# ble_shield.net
KiCad netlist of a schematic drawn in EAGLE
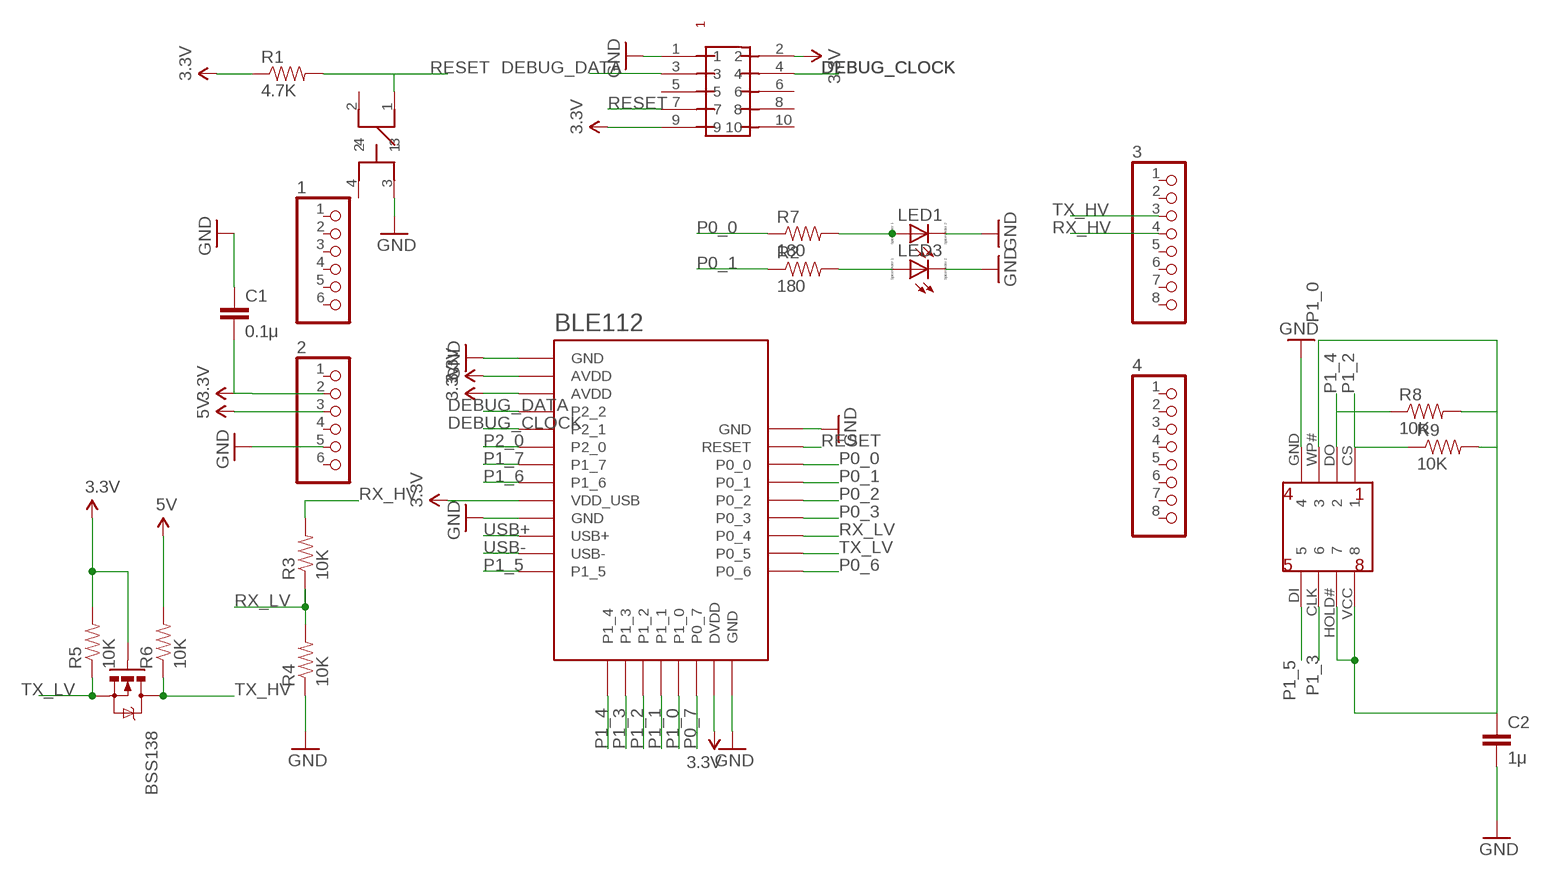
[diagram p0: schematic, sheet 1]

(export (version "E")
  (design (tool "Eeschema 10.0.6"))
  (components
    (comp (ref "1")
      (value "PINHD-1X6CB")
      (footprint "eagle-import:1X06-CLEANBIG")
      (libsource (lib "eagle-import") (part "PINHD-1X6CB"))
    )
    (comp (ref "2")
      (value "PINHD-1X6CB")
      (footprint "eagle-import:1X06-CLEANBIG")
      (libsource (lib "eagle-import") (part "PINHD-1X6CB"))
    )
    (comp (ref "3")
      (value "PINHD-1X8CLEANBIG")
      (footprint "eagle-import:1X08-CLEANBIG")
      (libsource (lib "eagle-import") (part "PINHD-1X8CLEANBIG"))
    )
    (comp (ref "4")
      (value "PINHD-1X8CLEANBIG")
      (footprint "eagle-import:1X08-CLEANBIG")
      (libsource (lib "eagle-import") (part "PINHD-1X8CLEANBIG"))
    )
    (comp (ref "BLE112")
      (value "SF-BLUEGIGA_BLE112-A-VISUAL")
      (footprint "eagle-import:SF-BLUEGIGA_BLE112-A")
      (libsource (lib "eagle-import") (part "SF-BLUEGIGA_BLE112-A-VISUAL"))
    )
    (comp (ref "BSS138")
      (value "MOSFET-NCHANNELSMD")
      (footprint "eagle-import:SOT23-3")
      (libsource (lib "eagle-import") (part "MOSFET-NCHANNELSMD"))
    )
    (comp (ref "C1")
      (value "0.1μ")
      (footprint "eagle-import:0603-CAP")
      (libsource (lib "eagle-import") (part "CAP0603-CAP"))
    )
    (comp (ref "C2")
      (value "1μ")
      (footprint "eagle-import:0603-CAP")
      (libsource (lib "eagle-import") (part "CAP0603-CAP"))
    )
    (comp (ref "LED1")
      (value "LED_ESML0603")
      (footprint "eagle-import:LED_SML0603")
      (libsource (lib "eagle-import") (part "LED_ESML0603"))
    )
    (comp (ref "LED3")
      (value "LED_ESML0603")
      (footprint "eagle-import:LED_SML0603")
      (libsource (lib "eagle-import") (part "LED_ESML0603"))
    )
    (comp (ref "R1")
      (value "4.7K")
      (footprint "eagle-import:0603-RES")
      (libsource (lib "eagle-import") (part "RESISTOR0603-RES"))
    )
    (comp (ref "R2")
      (value "180")
      (footprint "eagle-import:0603-RES")
      (libsource (lib "eagle-import") (part "RESISTOR0603-RES"))
    )
    (comp (ref "R3")
      (value "10K")
      (footprint "eagle-import:0603-RES")
      (libsource (lib "eagle-import") (part "RESISTOR0603-RES"))
    )
    (comp (ref "R4")
      (value "10K")
      (footprint "eagle-import:0603-RES")
      (libsource (lib "eagle-import") (part "RESISTOR0603-RES"))
    )
    (comp (ref "R5")
      (value "10K")
      (footprint "eagle-import:0603-RES")
      (libsource (lib "eagle-import") (part "RESISTOR0603-RES"))
    )
    (comp (ref "R6")
      (value "10K")
      (footprint "eagle-import:0603-RES")
      (libsource (lib "eagle-import") (part "RESISTOR0603-RES"))
    )
    (comp (ref "R7")
      (value "180")
      (footprint "eagle-import:0603-RES")
      (libsource (lib "eagle-import") (part "RESISTOR0603-RES"))
    )
    (comp (ref "R8")
      (value "10K")
      (footprint "eagle-import:0603-RES")
      (libsource (lib "eagle-import") (part "RESISTOR0603-RES"))
    )
    (comp (ref "R9")
      (value "10K")
      (footprint "eagle-import:0603-RES")
      (libsource (lib "eagle-import") (part "RESISTOR0603-RES"))
    )
    (comp (ref "U$1")
      (value "PIN-HEADER-SMT(1.27MM)2X5")
      (footprint "eagle-import:PIN-HEADER-SMT(1.27MM)2X5")
      (libsource (lib "eagle-import") (part "PIN-HEADER-SMT(1.27MM)2X5"))
    )
    (comp (ref "U$4")
      (value "SWITCH-LS6J2M-T")
      (footprint "eagle-import:SWICTH-LS6J2M-T")
      (libsource (lib "eagle-import") (part "SWITCH-LS6J2M-T"))
    )
    (comp (ref "U$7")
      (value "FLASH-MEMORY-2M(WINBOND)")
      (footprint "eagle-import:FLASH-MEMORY-2M(WINBOND)")
      (libsource (lib "eagle-import") (part "FLASH-MEMORY-2M(WINBOND)"))
    )
  )
  (nets
    (net (code "1") (name "/DEBUG_CLOCK") (class "Default")
      (node (ref "BLE112") (pin "P2_1") (pinfunction "P2_1_P2_1") (pintype "bidirectional"))
      (node (ref "U$1") (pin "4") (pinfunction "4_4") (pintype "bidirectional"))
    )
    (net (code "2") (name "/DEBUG_DATA") (class "Default")
      (node (ref "BLE112") (pin "P2_2") (pinfunction "P2_2_P2_2") (pintype "bidirectional"))
      (node (ref "U$1") (pin "3") (pinfunction "3_3") (pintype "bidirectional"))
    )
    (net (code "3") (name "/P0_0") (class "Default")
      (node (ref "BLE112") (pin "P0_0") (pinfunction "P0_0_P0_0") (pintype "bidirectional"))
      (node (ref "R7") (pin "1") (pinfunction "1_1") (pintype "passive"))
    )
    (net (code "4") (name "/P0_1") (class "Default")
      (node (ref "BLE112") (pin "P0_1") (pinfunction "P0_1_P0_1") (pintype "bidirectional"))
      (node (ref "R2") (pin "1") (pinfunction "1_1") (pintype "passive"))
    )
    (net (code "5") (name "/P0_2") (class "Default")
      (node (ref "BLE112") (pin "P0_2") (pinfunction "P0_2_P0_2") (pintype "bidirectional"))
    )
    (net (code "6") (name "/P0_3") (class "Default")
      (node (ref "BLE112") (pin "P0_3") (pinfunction "P0_3_P0_3") (pintype "bidirectional"))
    )
    (net (code "7") (name "/P0_6") (class "Default")
      (node (ref "BLE112") (pin "P0_6") (pinfunction "P0_6_P0_6") (pintype "bidirectional"))
    )
    (net (code "8") (name "/P0_7") (class "Default")
      (node (ref "BLE112") (pin "P0_7") (pinfunction "P0_7_P0_7") (pintype "bidirectional"))
    )
    (net (code "9") (name "/P1_0") (class "Default")
      (node (ref "BLE112") (pin "P1_0") (pinfunction "P1_0_P1_0") (pintype "bidirectional"))
      (node (ref "C2") (pin "1") (pinfunction "1_1") (pintype "passive"))
      (node (ref "R8") (pin "2") (pinfunction "2_2") (pintype "passive"))
      (node (ref "R9") (pin "2") (pinfunction "2_2") (pintype "passive"))
      (node (ref "U$7") (pin "HOLD#") (pinfunction "7_HOLD#") (pintype "bidirectional"))
      (node (ref "U$7") (pin "VCC") (pinfunction "8_VCC") (pintype "bidirectional"))
      (node (ref "U$7") (pin "WP#") (pinfunction "3_WP#") (pintype "bidirectional"))
    )
    (net (code "10") (name "/P1_1") (class "Default")
      (node (ref "BLE112") (pin "P1_1") (pinfunction "P1_1_P1_1") (pintype "bidirectional"))
    )
    (net (code "11") (name "/P1_2") (class "Default")
      (node (ref "BLE112") (pin "P1_2") (pinfunction "P1_2_P1_2") (pintype "bidirectional"))
      (node (ref "R9") (pin "1") (pinfunction "1_1") (pintype "passive"))
      (node (ref "U$7") (pin "CS") (pinfunction "1_CS") (pintype "bidirectional"))
    )
    (net (code "12") (name "/P1_3") (class "Default")
      (node (ref "BLE112") (pin "P1_3") (pinfunction "P1_3_P1_3") (pintype "bidirectional"))
      (node (ref "U$7") (pin "CLK") (pinfunction "6_CLK") (pintype "bidirectional"))
    )
    (net (code "13") (name "/P1_4") (class "Default")
      (node (ref "BLE112") (pin "P1_4") (pinfunction "P1_4_P1_4") (pintype "bidirectional"))
      (node (ref "R8") (pin "1") (pinfunction "1_1") (pintype "passive"))
      (node (ref "U$7") (pin "DO") (pinfunction "2_DO") (pintype "bidirectional"))
    )
    (net (code "14") (name "/P1_5") (class "Default")
      (node (ref "BLE112") (pin "P1_5") (pinfunction "P1_5_P1_5") (pintype "bidirectional"))
      (node (ref "U$7") (pin "DI") (pinfunction "5_DI") (pintype "bidirectional"))
    )
    (net (code "15") (name "/P1_6") (class "Default")
      (node (ref "BLE112") (pin "P1_6") (pinfunction "P1_6_P1_6") (pintype "bidirectional"))
    )
    (net (code "16") (name "/P1_7") (class "Default")
      (node (ref "BLE112") (pin "P1_7") (pinfunction "P1_7_P1_7") (pintype "bidirectional"))
    )
    (net (code "17") (name "/P2_0") (class "Default")
      (node (ref "BLE112") (pin "P2_0") (pinfunction "P2_0_P2_0") (pintype "bidirectional"))
    )
    (net (code "18") (name "/RESET") (class "Default")
      (node (ref "BLE112") (pin "RESET") (pinfunction "RESET_RESET") (pintype "input"))
      (node (ref "R1") (pin "2") (pinfunction "2_2") (pintype "passive"))
      (node (ref "U$1") (pin "7") (pinfunction "7_7") (pintype "bidirectional"))
      (node (ref "U$4") (pin "1") (pinfunction "1_1") (pintype "bidirectional"))
    )
    (net (code "19") (name "/RX_HV") (class "Default")
      (node (ref "3") (pin "4") (pinfunction "4_4") (pintype "passive"))
      (node (ref "R3") (pin "2") (pinfunction "2_2") (pintype "passive"))
    )
    (net (code "20") (name "/RX_LV") (class "Default")
      (node (ref "BLE112") (pin "P0_4") (pinfunction "P0_4_P0_4") (pintype "bidirectional"))
      (node (ref "R3") (pin "1") (pinfunction "1_1") (pintype "passive"))
      (node (ref "R4") (pin "2") (pinfunction "2_2") (pintype "passive"))
    )
    (net (code "21") (name "/TX_HV") (class "Default")
      (node (ref "3") (pin "3") (pinfunction "3_3") (pintype "passive"))
      (node (ref "BSS138") (pin "3") (pinfunction "D_3") (pintype "passive"))
      (node (ref "R6") (pin "1") (pinfunction "1_1") (pintype "passive"))
    )
    (net (code "22") (name "/TX_LV") (class "Default")
      (node (ref "BLE112") (pin "P0_5") (pinfunction "P0_5_P0_5") (pintype "bidirectional"))
      (node (ref "BSS138") (pin "2") (pinfunction "S_2") (pintype "passive"))
      (node (ref "R5") (pin "1") (pinfunction "1_1") (pintype "passive"))
    )
    (net (code "23") (name "/USB+") (class "Default")
      (node (ref "BLE112") (pin "USB+") (pinfunction "USB+_USB+") (pintype "bidirectional"))
    )
    (net (code "24") (name "/USB-") (class "Default")
      (node (ref "BLE112") (pin "USB-") (pinfunction "USB-_USB-") (pintype "bidirectional"))
    )
    (net (code "25") (name "3.3V") (class "Default")
      (node (ref "2") (pin "2") (pinfunction "2_2") (pintype "passive"))
      (node (ref "BLE112") (pin "AVDD1") (pinfunction "AVDD_AVDD1") (pintype "power_in"))
      (node (ref "BLE112") (pin "AVDD2") (pinfunction "AVDD_AVDD2") (pintype "power_in"))
      (node (ref "BLE112") (pin "DVDD") (pinfunction "DVDD_DVDD") (pintype "power_in"))
      (node (ref "BLE112") (pin "VDD_USB") (pinfunction "VDD_USB_VDD_USB") (pintype "power_in"))
      (node (ref "BSS138") (pin "1") (pinfunction "G_1") (pintype "passive"))
      (node (ref "C1") (pin "2") (pinfunction "2_2") (pintype "passive"))
      (node (ref "R1") (pin "1") (pinfunction "1_1") (pintype "passive"))
      (node (ref "R5") (pin "2") (pinfunction "2_2") (pintype "passive"))
      (node (ref "U$1") (pin "2") (pinfunction "2_2") (pintype "bidirectional"))
      (node (ref "U$1") (pin "9") (pinfunction "9_9") (pintype "bidirectional"))
    )
    (net (code "26") (name "5V") (class "Default")
      (node (ref "2") (pin "3") (pinfunction "3_3") (pintype "passive"))
      (node (ref "R6") (pin "2") (pinfunction "2_2") (pintype "passive"))
    )
    (net (code "27") (name "GND") (class "Default")
      (node (ref "2") (pin "5") (pinfunction "5_5") (pintype "passive"))
      (node (ref "BLE112") (pin "GND1") (pinfunction "GND_GND1") (pintype "power_in"))
      (node (ref "BLE112") (pin "GND2") (pinfunction "GND_GND2") (pintype "power_in"))
      (node (ref "BLE112") (pin "GND3") (pinfunction "GND_GND3") (pintype "power_in"))
      (node (ref "BLE112") (pin "GND4") (pinfunction "GND_GND4") (pintype "power_in"))
      (node (ref "C1") (pin "1") (pinfunction "1_1") (pintype "passive"))
      (node (ref "C2") (pin "2") (pinfunction "2_2") (pintype "passive"))
      (node (ref "LED1") (pin "C") (pinfunction "C_C") (pintype "passive"))
      (node (ref "LED3") (pin "C") (pinfunction "C_C") (pintype "passive"))
      (node (ref "R4") (pin "1") (pinfunction "1_1") (pintype "passive"))
      (node (ref "U$1") (pin "1") (pinfunction "1_1") (pintype "bidirectional"))
      (node (ref "U$4") (pin "3") (pinfunction "3_3") (pintype "bidirectional"))
      (node (ref "U$7") (pin "GND") (pinfunction "4_GND") (pintype "bidirectional"))
    )
    (net (code "28") (name "Net-(LED1-PadA)") (class "Default")
      (node (ref "LED1") (pin "A") (pinfunction "A_A") (pintype "passive"))
      (node (ref "R7") (pin "2") (pinfunction "2_2") (pintype "passive"))
    )
    (net (code "29") (name "Net-(LED3-PadA)") (class "Default")
      (node (ref "LED3") (pin "A") (pinfunction "A_A") (pintype "passive"))
      (node (ref "R2") (pin "2") (pinfunction "2_2") (pintype "passive"))
    )
    (net (code "30") (name "unconnected-(1-Pad1)") (class "Default")
      (node (ref "1") (pin "1") (pinfunction "1_1") (pintype "passive"))
    )
    (net (code "31") (name "unconnected-(1-Pad2)") (class "Default")
      (node (ref "1") (pin "2") (pinfunction "2_2") (pintype "passive"))
    )
    (net (code "32") (name "unconnected-(1-Pad3)") (class "Default")
      (node (ref "1") (pin "3") (pinfunction "3_3") (pintype "passive"))
    )
    (net (code "33") (name "unconnected-(1-Pad4)") (class "Default")
      (node (ref "1") (pin "4") (pinfunction "4_4") (pintype "passive"))
    )
    (net (code "34") (name "unconnected-(1-Pad5)") (class "Default")
      (node (ref "1") (pin "5") (pinfunction "5_5") (pintype "passive"))
    )
    (net (code "35") (name "unconnected-(1-Pad6)") (class "Default")
      (node (ref "1") (pin "6") (pinfunction "6_6") (pintype "passive"))
    )
    (net (code "36") (name "unconnected-(2-Pad1)") (class "Default")
      (node (ref "2") (pin "1") (pinfunction "1_1") (pintype "passive"))
    )
    (net (code "37") (name "unconnected-(2-Pad4)") (class "Default")
      (node (ref "2") (pin "4") (pinfunction "4_4") (pintype "passive"))
    )
    (net (code "38") (name "unconnected-(2-Pad6)") (class "Default")
      (node (ref "2") (pin "6") (pinfunction "6_6") (pintype "passive"))
    )
    (net (code "39") (name "unconnected-(3-Pad1)") (class "Default")
      (node (ref "3") (pin "1") (pinfunction "1_1") (pintype "passive"))
    )
    (net (code "40") (name "unconnected-(3-Pad2)") (class "Default")
      (node (ref "3") (pin "2") (pinfunction "2_2") (pintype "passive"))
    )
    (net (code "41") (name "unconnected-(3-Pad5)") (class "Default")
      (node (ref "3") (pin "5") (pinfunction "5_5") (pintype "passive"))
    )
    (net (code "42") (name "unconnected-(3-Pad6)") (class "Default")
      (node (ref "3") (pin "6") (pinfunction "6_6") (pintype "passive"))
    )
    (net (code "43") (name "unconnected-(3-Pad7)") (class "Default")
      (node (ref "3") (pin "7") (pinfunction "7_7") (pintype "passive"))
    )
    (net (code "44") (name "unconnected-(3-Pad8)") (class "Default")
      (node (ref "3") (pin "8") (pinfunction "8_8") (pintype "passive"))
    )
    (net (code "45") (name "unconnected-(4-Pad1)") (class "Default")
      (node (ref "4") (pin "1") (pinfunction "1_1") (pintype "passive"))
    )
    (net (code "46") (name "unconnected-(4-Pad2)") (class "Default")
      (node (ref "4") (pin "2") (pinfunction "2_2") (pintype "passive"))
    )
    (net (code "47") (name "unconnected-(4-Pad3)") (class "Default")
      (node (ref "4") (pin "3") (pinfunction "3_3") (pintype "passive"))
    )
    (net (code "48") (name "unconnected-(4-Pad4)") (class "Default")
      (node (ref "4") (pin "4") (pinfunction "4_4") (pintype "passive"))
    )
    (net (code "49") (name "unconnected-(4-Pad5)") (class "Default")
      (node (ref "4") (pin "5") (pinfunction "5_5") (pintype "passive"))
    )
    (net (code "50") (name "unconnected-(4-Pad6)") (class "Default")
      (node (ref "4") (pin "6") (pinfunction "6_6") (pintype "passive"))
    )
    (net (code "51") (name "unconnected-(4-Pad7)") (class "Default")
      (node (ref "4") (pin "7") (pinfunction "7_7") (pintype "passive"))
    )
    (net (code "52") (name "unconnected-(4-Pad8)") (class "Default")
      (node (ref "4") (pin "8") (pinfunction "8_8") (pintype "passive"))
    )
    (net (code "53") (name "unconnected-(U$1-Pad5)") (class "Default")
      (node (ref "U$1") (pin "5") (pinfunction "5_5") (pintype "bidirectional"))
    )
    (net (code "54") (name "unconnected-(U$1-Pad6)") (class "Default")
      (node (ref "U$1") (pin "6") (pinfunction "6_6") (pintype "bidirectional"))
    )
    (net (code "55") (name "unconnected-(U$1-Pad8)") (class "Default")
      (node (ref "U$1") (pin "8") (pinfunction "8_8") (pintype "bidirectional"))
    )
    (net (code "56") (name "unconnected-(U$1-Pad10)") (class "Default")
      (node (ref "U$1") (pin "10") (pinfunction "10_10") (pintype "bidirectional"))
    )
    (net (code "57") (name "unconnected-(U$4-Pad2)") (class "Default")
      (node (ref "U$4") (pin "2") (pinfunction "2_2") (pintype "bidirectional"))
    )
    (net (code "58") (name "unconnected-(U$4-Pad4)") (class "Default")
      (node (ref "U$4") (pin "4") (pinfunction "4_4") (pintype "bidirectional"))
    )
  )
)
